# untitled.net
KiCad netlist of a schematic drawn in EAGLE
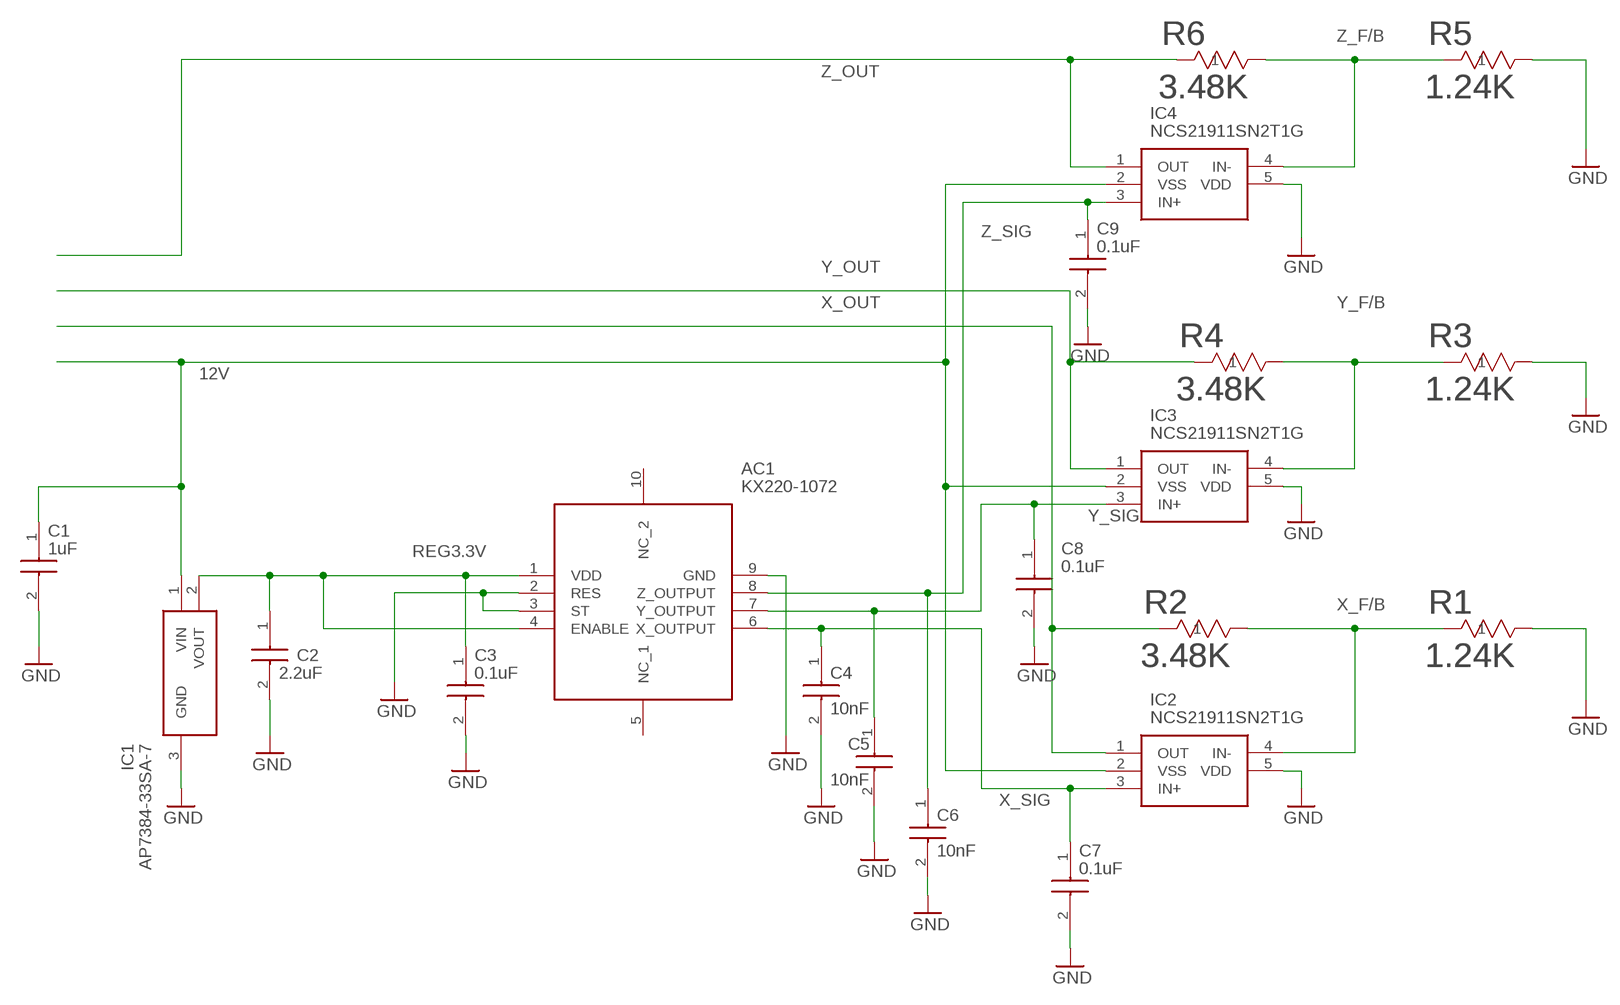
[diagram p0: schematic, sheet 1]

(export (version "E")
  (design (tool "Eeschema 10.0.6"))
  (components
    (comp (ref "AC1")
      (value "KX220-1072")
      (footprint "eagle-import:KX2201072")
      (fields (field (name "MOUSER_PART_NUMBER") "912-KX220-1072"))
      (libsource (lib "eagle-import") (part "KX220-1072"))
    )
    (comp (ref "C1")
      (value "1uF")
      (footprint "eagle-import:CAPC1608X90N")
      (fields
        (field (name "MANUFACTURER_PART_NUMBER") "CGA3E1X7R1V105K080AE")
        (field (name "MOUSER_PART_NUMBER") "810-CGA3E1X7R1V105KA")
      )
      (libsource (lib "eagle-import") (part "CGA3E1X7R1V105K080AE"))
    )
    (comp (ref "C2")
      (value "2.2uF")
      (footprint "eagle-import:CAPC1608X90N")
      (fields
        (field (name "MANUFACTURER_PART_NUMBER") "CGA3E1X7R0J225K080AC")
        (field (name "MOUSER_PART_NUMBER") "810-CGA3E1X7R0J225K")
      )
      (libsource (lib "eagle-import") (part "CGA3E1X7R0J225K080AC"))
    )
    (comp (ref "C3")
      (value "0.1uF")
      (footprint "eagle-import:CAPC1608X90N")
      (fields
        (field (name "MANUFACTURER_PART_NUMBER") "CGA3E2X7R1H104K080AE")
        (field (name "MOUSER_PART_NUMBER") "810-CGA3E2X7R1H104KE")
      )
      (libsource (lib "eagle-import") (part "CGA3E2X7R1H104K080AE"))
    )
    (comp (ref "C4")
      (value "10nF")
      (footprint "eagle-import:CAPC1608X90N")
      (fields
        (field (name "MANUFACTURER_PART_NUMBER") "CGA3E1C0G2A103J080AE")
        (field (name "MOUSER_PART_NUMBER") "810-CGA3E1C0G2A103J0")
      )
      (libsource (lib "eagle-import") (part "CGA3E1C0G2A103J080AE"))
    )
    (comp (ref "C5")
      (value "10nF")
      (footprint "eagle-import:CAPC1608X90N")
      (fields
        (field (name "MANUFACTURER_PART_NUMBER") "CGA3E1C0G2A103J080AE")
        (field (name "MOUSER_PART_NUMBER") "810-CGA3E1C0G2A103J0")
      )
      (libsource (lib "eagle-import") (part "CGA3E1C0G2A103J080AE"))
    )
    (comp (ref "C6")
      (value "10nF")
      (footprint "eagle-import:CAPC1608X90N")
      (fields
        (field (name "MANUFACTURER_PART_NUMBER") "CGA3E1C0G2A103J080AE")
        (field (name "MOUSER_PART_NUMBER") "810-CGA3E1C0G2A103J0")
      )
      (libsource (lib "eagle-import") (part "CGA3E1C0G2A103J080AE"))
    )
    (comp (ref "C7")
      (value "0.1uF")
      (footprint "eagle-import:CAPC1608X90N")
      (fields
        (field (name "MANUFACTURER_PART_NUMBER") "CGA3E2X7R1H104K080AE")
        (field (name "MOUSER_PART_NUMBER") "810-CGA3E2X7R1H104KE")
      )
      (libsource (lib "eagle-import") (part "CGA3E2X7R1H104K080AE"))
    )
    (comp (ref "C8")
      (value "0.1uF")
      (footprint "eagle-import:CAPC1608X90N")
      (fields
        (field (name "MANUFACTURER_PART_NUMBER") "CGA3E2X7R1H104K080AE")
        (field (name "MOUSER_PART_NUMBER") "810-CGA3E2X7R1H104KE")
      )
      (libsource (lib "eagle-import") (part "CGA3E2X7R1H104K080AE"))
    )
    (comp (ref "C9")
      (value "0.1uF")
      (footprint "eagle-import:CAPC1608X90N")
      (fields
        (field (name "MANUFACTURER_PART_NUMBER") "CGA3E2X7R1H104K080AE")
        (field (name "MOUSER_PART_NUMBER") "810-CGA3E2X7R1H104KE")
      )
      (libsource (lib "eagle-import") (part "CGA3E2X7R1H104K080AE"))
    )
    (comp (ref "IC1")
      (value "AP7384-33SA-7")
      (footprint "eagle-import:SOT96P240X110-3N")
      (fields (field (name "MOUSER_PART_NUMBER") "621-AP7384-33SA-7"))
      (libsource (lib "eagle-import") (part "AP7384-33SA-7"))
    )
    (comp (ref "IC2")
      (value "NCS21911SN2T1G")
      (footprint "eagle-import:SOT95P275X110-5N")
      (fields (field (name "MOUSER_PART_NUMBER") "863-NCS21911SN2T1G"))
      (libsource (lib "eagle-import") (part "NCS21911SN2T1G"))
    )
    (comp (ref "IC3")
      (value "NCS21911SN2T1G")
      (footprint "eagle-import:SOT95P275X110-5N")
      (fields (field (name "MOUSER_PART_NUMBER") "863-NCS21911SN2T1G"))
      (libsource (lib "eagle-import") (part "NCS21911SN2T1G"))
    )
    (comp (ref "IC4")
      (value "NCS21911SN2T1G")
      (footprint "eagle-import:SOT95P275X110-5N")
      (fields (field (name "MOUSER_PART_NUMBER") "863-NCS21911SN2T1G"))
      (libsource (lib "eagle-import") (part "NCS21911SN2T1G"))
    )
    (comp (ref "R1")
      (value "1.24K")
      (footprint "eagle-import:RES_TNPW0402_VIS")
      (fields
        (field (name "MANUFACTURER_PART_NUMBER") "TNPW04021K24BEED")
        (field (name "COPYRIGHT") "Copyright (C) 2022 Ultra Librarian. All rights reserved.")
      )
      (libsource (lib "eagle-import") (part "TNPW04021K24BEED"))
    )
    (comp (ref "R2")
      (value "3.48K")
      (footprint "eagle-import:RES_TNPW0402_VIS")
      (fields
        (field (name "MANUFACTURER_PART_NUMBER") "TNPW04023K48BEED")
        (field (name "COPYRIGHT") "Copyright (C) 2022 Ultra Librarian. All rights reserved.")
      )
      (libsource (lib "eagle-import") (part "TNPW04023K48BEED"))
    )
    (comp (ref "R3")
      (value "1.24K")
      (footprint "eagle-import:RES_TNPW0402_VIS")
      (fields
        (field (name "MANUFACTURER_PART_NUMBER") "TNPW04021K24BEED")
        (field (name "COPYRIGHT") "Copyright (C) 2022 Ultra Librarian. All rights reserved.")
      )
      (libsource (lib "eagle-import") (part "TNPW04021K24BEED"))
    )
    (comp (ref "R4")
      (value "3.48K")
      (footprint "eagle-import:RES_TNPW0402_VIS")
      (fields
        (field (name "MANUFACTURER_PART_NUMBER") "TNPW04023K48BEED")
        (field (name "COPYRIGHT") "Copyright (C) 2022 Ultra Librarian. All rights reserved.")
      )
      (libsource (lib "eagle-import") (part "TNPW04023K48BEED"))
    )
    (comp (ref "R5")
      (value "1.24K")
      (footprint "eagle-import:RES_TNPW0402_VIS")
      (fields
        (field (name "MANUFACTURER_PART_NUMBER") "TNPW04021K24BEED")
        (field (name "COPYRIGHT") "Copyright (C) 2022 Ultra Librarian. All rights reserved.")
      )
      (libsource (lib "eagle-import") (part "TNPW04021K24BEED"))
    )
    (comp (ref "R6")
      (value "3.48K")
      (footprint "eagle-import:RES_TNPW0402_VIS")
      (fields
        (field (name "MANUFACTURER_PART_NUMBER") "TNPW04023K48BEED")
        (field (name "COPYRIGHT") "Copyright (C) 2022 Ultra Librarian. All rights reserved.")
      )
      (libsource (lib "eagle-import") (part "TNPW04023K48BEED"))
    )
  )
  (nets
    (net (code "1") (name "/12V") (class "Default")
      (node (ref "C1") (pin "1") (pinfunction "1_1") (pintype "bidirectional"))
      (node (ref "IC1") (pin "1") (pinfunction "VIN_1") (pintype "bidirectional"))
      (node (ref "IC2") (pin "2") (pinfunction "VSS_2") (pintype "bidirectional"))
      (node (ref "IC3") (pin "2") (pinfunction "VSS_2") (pintype "bidirectional"))
      (node (ref "IC4") (pin "2") (pinfunction "VSS_2") (pintype "bidirectional"))
    )
    (net (code "2") (name "/REG3.3V") (class "Default")
      (node (ref "AC1") (pin "1") (pinfunction "VDD_1") (pintype "bidirectional"))
      (node (ref "AC1") (pin "4") (pinfunction "ENABLE_4") (pintype "bidirectional"))
      (node (ref "C2") (pin "1") (pinfunction "1_1") (pintype "bidirectional"))
      (node (ref "C3") (pin "1") (pinfunction "1_1") (pintype "bidirectional"))
      (node (ref "IC1") (pin "2") (pinfunction "VOUT_2") (pintype "bidirectional"))
    )
    (net (code "3") (name "/X_F{slash}B") (class "Default")
      (node (ref "IC2") (pin "4") (pinfunction "IN-_4") (pintype "bidirectional"))
      (node (ref "R1") (pin "1") (pinfunction "1_1") (pintype "passive"))
      (node (ref "R2") (pin "2") (pinfunction "2_2") (pintype "passive"))
    )
    (net (code "4") (name "/X_OUT") (class "Default")
      (node (ref "IC2") (pin "1") (pinfunction "OUT_1") (pintype "bidirectional"))
      (node (ref "R2") (pin "1") (pinfunction "1_1") (pintype "passive"))
    )
    (net (code "5") (name "/X_SIG") (class "Default")
      (node (ref "AC1") (pin "6") (pinfunction "X_OUTPUT_6") (pintype "bidirectional"))
      (node (ref "C4") (pin "1") (pinfunction "1_1") (pintype "bidirectional"))
      (node (ref "C7") (pin "1") (pinfunction "1_1") (pintype "bidirectional"))
      (node (ref "IC2") (pin "3") (pinfunction "IN+_3") (pintype "bidirectional"))
    )
    (net (code "6") (name "/Y_F{slash}B") (class "Default")
      (node (ref "IC3") (pin "4") (pinfunction "IN-_4") (pintype "bidirectional"))
      (node (ref "R3") (pin "1") (pinfunction "1_1") (pintype "passive"))
      (node (ref "R4") (pin "2") (pinfunction "2_2") (pintype "passive"))
    )
    (net (code "7") (name "/Y_OUT") (class "Default")
      (node (ref "IC3") (pin "1") (pinfunction "OUT_1") (pintype "bidirectional"))
      (node (ref "R4") (pin "1") (pinfunction "1_1") (pintype "passive"))
    )
    (net (code "8") (name "/Y_SIG") (class "Default")
      (node (ref "AC1") (pin "7") (pinfunction "Y_OUTPUT_7") (pintype "bidirectional"))
      (node (ref "C5") (pin "1") (pinfunction "1_1") (pintype "bidirectional"))
      (node (ref "C8") (pin "1") (pinfunction "1_1") (pintype "bidirectional"))
      (node (ref "IC3") (pin "3") (pinfunction "IN+_3") (pintype "bidirectional"))
    )
    (net (code "9") (name "/Z_F{slash}B") (class "Default")
      (node (ref "IC4") (pin "4") (pinfunction "IN-_4") (pintype "bidirectional"))
      (node (ref "R5") (pin "1") (pinfunction "1_1") (pintype "passive"))
      (node (ref "R6") (pin "2") (pinfunction "2_2") (pintype "passive"))
    )
    (net (code "10") (name "/Z_OUT") (class "Default")
      (node (ref "IC4") (pin "1") (pinfunction "OUT_1") (pintype "bidirectional"))
      (node (ref "R6") (pin "1") (pinfunction "1_1") (pintype "passive"))
    )
    (net (code "11") (name "/Z_SIG") (class "Default")
      (node (ref "AC1") (pin "8") (pinfunction "Z_OUTPUT_8") (pintype "bidirectional"))
      (node (ref "C6") (pin "1") (pinfunction "1_1") (pintype "bidirectional"))
      (node (ref "C9") (pin "1") (pinfunction "1_1") (pintype "bidirectional"))
      (node (ref "IC4") (pin "3") (pinfunction "IN+_3") (pintype "bidirectional"))
    )
    (net (code "12") (name "GND") (class "Default")
      (node (ref "AC1") (pin "2") (pinfunction "RES_2") (pintype "bidirectional"))
      (node (ref "AC1") (pin "3") (pinfunction "ST_3") (pintype "bidirectional"))
      (node (ref "AC1") (pin "9") (pinfunction "GND_9") (pintype "bidirectional"))
      (node (ref "C1") (pin "2") (pinfunction "2_2") (pintype "bidirectional"))
      (node (ref "C2") (pin "2") (pinfunction "2_2") (pintype "bidirectional"))
      (node (ref "C3") (pin "2") (pinfunction "2_2") (pintype "bidirectional"))
      (node (ref "C4") (pin "2") (pinfunction "2_2") (pintype "bidirectional"))
      (node (ref "C5") (pin "2") (pinfunction "2_2") (pintype "bidirectional"))
      (node (ref "C6") (pin "2") (pinfunction "2_2") (pintype "bidirectional"))
      (node (ref "C7") (pin "2") (pinfunction "2_2") (pintype "bidirectional"))
      (node (ref "C8") (pin "2") (pinfunction "2_2") (pintype "bidirectional"))
      (node (ref "C9") (pin "2") (pinfunction "2_2") (pintype "bidirectional"))
      (node (ref "IC1") (pin "3") (pinfunction "GND_3") (pintype "bidirectional"))
      (node (ref "IC2") (pin "5") (pinfunction "VDD_5") (pintype "bidirectional"))
      (node (ref "IC3") (pin "5") (pinfunction "VDD_5") (pintype "bidirectional"))
      (node (ref "IC4") (pin "5") (pinfunction "VDD_5") (pintype "bidirectional"))
      (node (ref "R1") (pin "2") (pinfunction "2_2") (pintype "passive"))
      (node (ref "R3") (pin "2") (pinfunction "2_2") (pintype "passive"))
      (node (ref "R5") (pin "2") (pinfunction "2_2") (pintype "passive"))
    )
    (net (code "13") (name "unconnected-(AC1-NC_1-Pad5)") (class "Default")
      (node (ref "AC1") (pin "5") (pinfunction "NC_1_5") (pintype "bidirectional"))
    )
    (net (code "14") (name "unconnected-(AC1-NC_2-Pad10)") (class "Default")
      (node (ref "AC1") (pin "10") (pinfunction "NC_2_10") (pintype "bidirectional"))
    )
  )
)
